# BluJoy-e.net
KiCad netlist of a schematic drawn in EAGLE
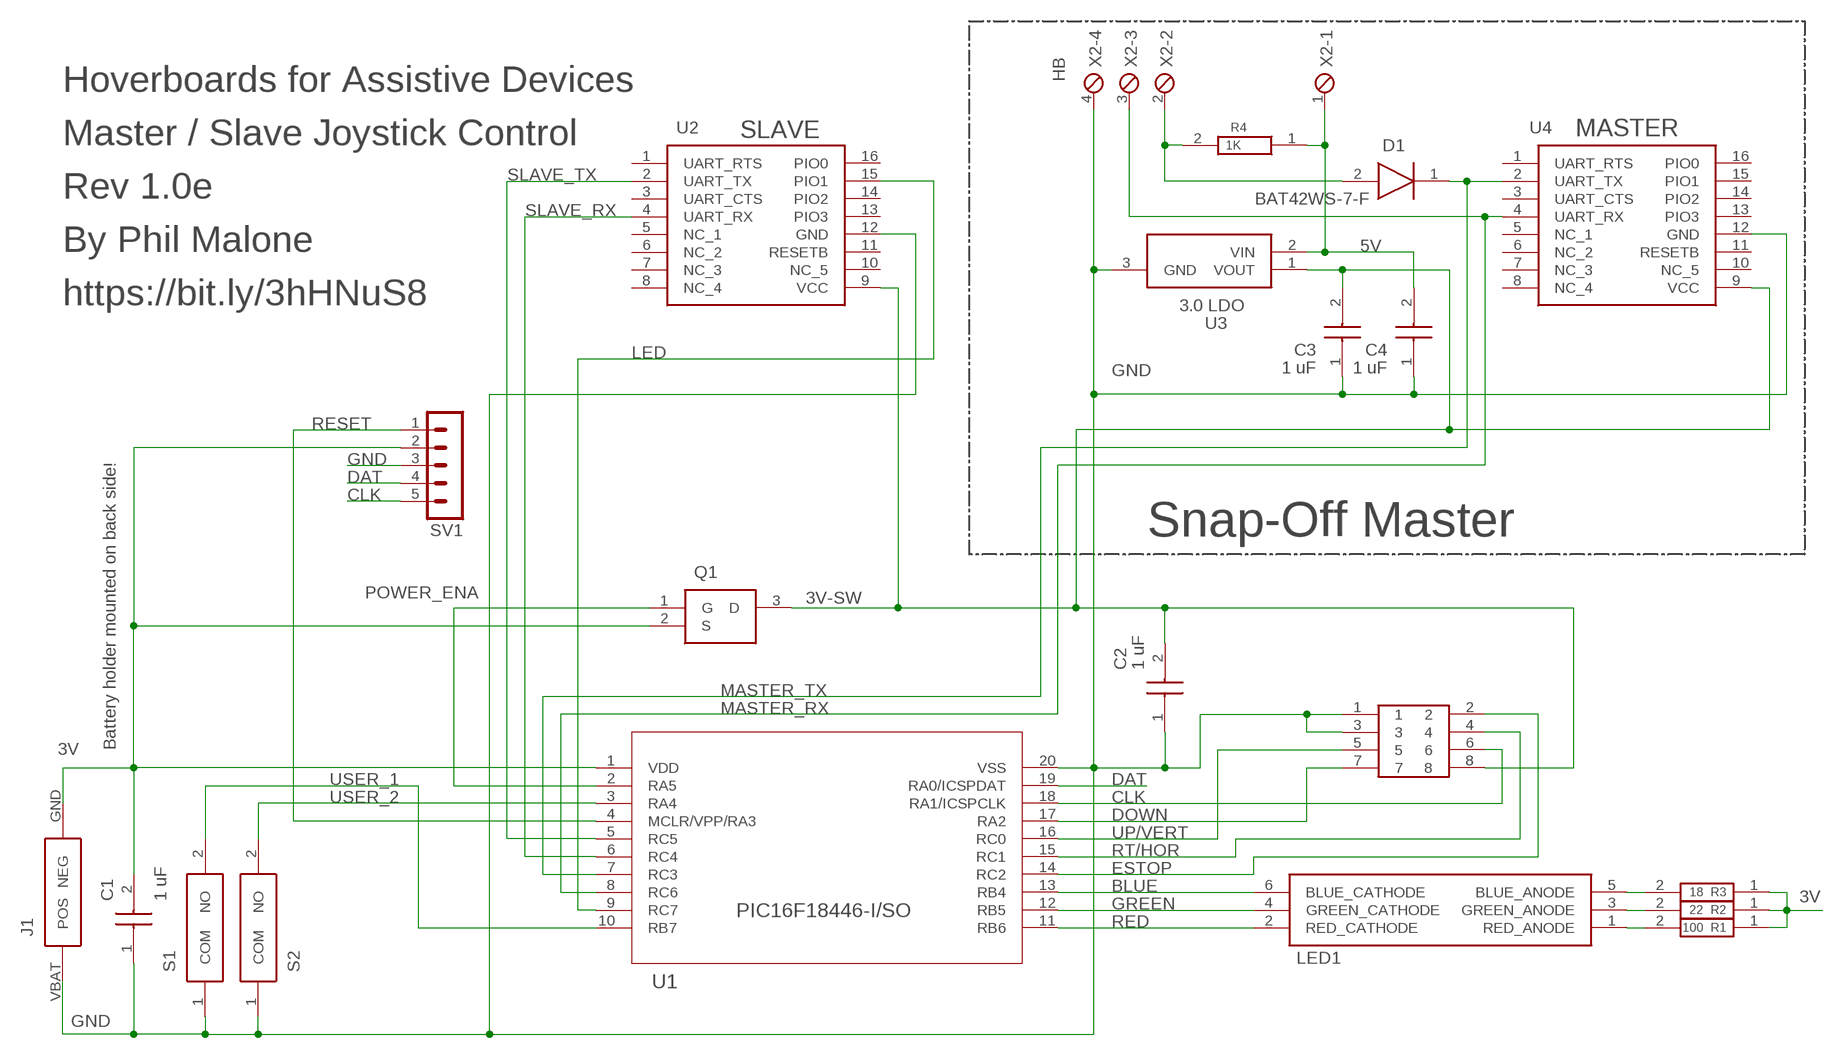
[diagram p0: schematic, sheet 1]

(export (version "E")
  (design (tool "Eeschema 10.0.6"))
  (components
    (comp (ref "C1")
      (value "1 uF")
      (footprint "eagle-import:CAPC1608X90N")
      (fields
        (field (name "MANUFACTURER_PART_NUMBER") "CC0603KRX7R7BB104")
        (field (name "MOUSER_PART_NUMBER") "603-CC603KRX7R7BB104")
        (field (name "RS_PART_NUMBER") "6698763")
      )
      (libsource (lib "eagle-import") (part "CC0603KRX7R7BB104"))
    )
    (comp (ref "C2")
      (value "1 uF")
      (footprint "eagle-import:CAPC1608X90N")
      (fields
        (field (name "MANUFACTURER_PART_NUMBER") "CC0603KRX7R7BB104")
        (field (name "MOUSER_PART_NUMBER") "603-CC603KRX7R7BB104")
        (field (name "RS_PART_NUMBER") "6698763")
      )
      (libsource (lib "eagle-import") (part "CC0603KRX7R7BB104"))
    )
    (comp (ref "C3")
      (value "1 uF")
      (footprint "eagle-import:CAPC1608X90N")
      (fields
        (field (name "MANUFACTURER_PART_NUMBER") "CC0603KRX7R7BB104")
        (field (name "MOUSER_PART_NUMBER") "603-CC603KRX7R7BB104")
        (field (name "RS_PART_NUMBER") "6698763")
      )
      (libsource (lib "eagle-import") (part "CC0603KRX7R7BB104"))
    )
    (comp (ref "C4")
      (value "1 uF")
      (footprint "eagle-import:CAPC1608X90N")
      (fields
        (field (name "MANUFACTURER_PART_NUMBER") "CC0603KRX7R7BB104")
        (field (name "MOUSER_PART_NUMBER") "603-CC603KRX7R7BB104")
        (field (name "RS_PART_NUMBER") "6698763")
      )
      (libsource (lib "eagle-import") (part "CC0603KRX7R7BB104"))
    )
    (comp (ref "D1")
      (value "BAT42WS-7-F")
      (footprint "eagle-import:SOD2513X120N")
      (fields (field (name "MOUSER_PART_NUMBER") "621-BAT42WS-F"))
      (libsource (lib "eagle-import") (part "BAT42WS-7-F"))
    )
    (comp (ref "J1")
      (value "2468")
      (footprint "eagle-import:2468")
      (fields (field (name "MOUSER_PART_NUMBER") "534-2468") (field (name "RS_PART_NUMBER") "2794965"))
      (libsource (lib "eagle-import") (part "2468"))
    )
    (comp (ref "LED1")
      (value "ASMB-TTF0-0A20B")
      (footprint "eagle-import:ASMBTTF00A20B")
      (fields (field (name "MOUSER_PART_NUMBER") "630-ASMB-TTF0-0A20B"))
      (libsource (lib "eagle-import") (part "ASMB-TTF0-0A20B"))
    )
    (comp (ref "Q1")
      (value "P-FET")
      (footprint "eagle-import:SOT96P237X111-3N")
      (fields
        (field (name "ARROW_PART_NUMBER") "NTR4171PT1G")
        (field (name "MOUSER_PART_NUMBER") "863-NTR4171PT1G")
      )
      (libsource (lib "eagle-import") (part "NTR4171PT1G"))
    )
    (comp (ref "R1")
      (value "100")
      (footprint "eagle-import:RESC1608X50N")
      (fields
        (field (name "MANUFACTURER_PART_NUMBER") "CRCW0603240RFKEB")
        (field (name "MOUSER_PART_NUMBER") "71-CRCW0603240RFKEB")
      )
      (libsource (lib "eagle-import") (part "CRCW0603240RFKEB"))
    )
    (comp (ref "R2")
      (value "22")
      (footprint "eagle-import:RESC1608X50N")
      (fields
        (field (name "MANUFACTURER_PART_NUMBER") "CRCW0603240RFKEB")
        (field (name "MOUSER_PART_NUMBER") "71-CRCW0603240RFKEB")
      )
      (libsource (lib "eagle-import") (part "CRCW0603240RFKEB"))
    )
    (comp (ref "R3")
      (value "18")
      (footprint "eagle-import:RESC1608X50N")
      (fields
        (field (name "MANUFACTURER_PART_NUMBER") "CRCW0603240RFKEB")
        (field (name "MOUSER_PART_NUMBER") "71-CRCW0603240RFKEB")
      )
      (libsource (lib "eagle-import") (part "CRCW0603240RFKEB"))
    )
    (comp (ref "R4")
      (value "1K")
      (footprint "eagle-import:RESC1608X50N")
      (fields
        (field (name "MANUFACTURER_PART_NUMBER") "CRCW0603240RFKEB")
        (field (name "MOUSER_PART_NUMBER") "71-CRCW0603240RFKEB")
      )
      (libsource (lib "eagle-import") (part "CRCW0603240RFKEB"))
    )
    (comp (ref "S1")
      (value "PTS636_SK25J_SMTR_LFS")
      (footprint "eagle-import:PTS636SK25JSMTRLFS")
      (fields
        (field (name "MANUFACTURER_PART_NUMBER") "PTS636 SK25J SMTR LFS")
        (field (name "MOUSER_PART_NUMBER") "611-PTS636SK25JSMTRL")
      )
      (libsource (lib "eagle-import") (part "PTS636_SK25J_SMTR_LFS"))
    )
    (comp (ref "S2")
      (value "PTS636_SK25J_SMTR_LFS")
      (footprint "eagle-import:PTS636SK25JSMTRLFS")
      (fields
        (field (name "MANUFACTURER_PART_NUMBER") "PTS636 SK25J SMTR LFS")
        (field (name "MOUSER_PART_NUMBER") "611-PTS636SK25JSMTRL")
      )
      (libsource (lib "eagle-import") (part "PTS636_SK25J_SMTR_LFS"))
    )
    (comp (ref "SV1")
      (value "PICKIT")
      (footprint "eagle-import:MA05-1")
      (libsource (lib "eagle-import") (part "PICKIT"))
    )
    (comp (ref "U$2")
      (value "PHOENIX3.5X8-B")
      (footprint "eagle-import:1751303")
      (libsource (lib "eagle-import") (part "PHOENIX3.5X8-B"))
    )
    (comp (ref "U1")
      (value "PIC16F18446-I/SO")
      (footprint "eagle-import:SOIC20_SO_MCH")
      (fields
        (field (name "MANUFACTURER_PART_NUMBER") "PIC16F15345-I/SO")
        (field (name "COPYRIGHT") "Copyright (C) 2018 Accelerated Designs. All rights reserved")
      )
      (libsource (lib "eagle-import") (part "PIC16F15345-I/SO"))
    )
    (comp (ref "U2")
      (value "HM-11")
      (footprint "eagle-import:HM-11-MODULE")
      (libsource (lib "eagle-import") (part "HM-11"))
    )
    (comp (ref "U3")
      (value "3.0 LDO")
      (footprint "eagle-import:SOT95P237X112-3N")
      (fields
        (field (name "ARROW_PART_NUMBER") "MCP1812AT-030/TT")
        (field (name "MOUSER_PART_NUMBER") "579-MCP1812AT-030/TT")
      )
      (libsource (lib "eagle-import") (part "MCP1812AT-030_TT"))
    )
    (comp (ref "U4")
      (value "HM-11")
      (footprint "eagle-import:HM-11-MODULE")
      (libsource (lib "eagle-import") (part "HM-11"))
    )
    (comp (ref "X2")
      (value "HB")
      (footprint "eagle-import:4POL254")
      (libsource (lib "eagle-import") (part "MPT4"))
    )
  )
  (nets
    (net (code "1") (name "/3V") (class "Default")
      (node (ref "C1") (pin "2") (pinfunction "C2_2") (pintype "bidirectional"))
      (node (ref "J1") (pin "GND") (pinfunction "NEG_GND") (pintype "bidirectional"))
      (node (ref "Q1") (pin "2") (pinfunction "S_2") (pintype "bidirectional"))
      (node (ref "R1") (pin "1") (pinfunction "1_1") (pintype "bidirectional"))
      (node (ref "R2") (pin "1") (pinfunction "1_1") (pintype "bidirectional"))
      (node (ref "R3") (pin "1") (pinfunction "1_1") (pintype "bidirectional"))
      (node (ref "SV1") (pin "2") (pinfunction "2_2") (pintype "passive"))
      (node (ref "U1") (pin "1") (pinfunction "VDD_1") (pintype "power_in"))
    )
    (net (code "2") (name "/3V-SW") (class "Default")
      (node (ref "C2") (pin "2") (pinfunction "C2_2") (pintype "bidirectional"))
      (node (ref "C3") (pin "2") (pinfunction "C2_2") (pintype "bidirectional"))
      (node (ref "Q1") (pin "3") (pinfunction "D_3") (pintype "bidirectional"))
      (node (ref "U$2") (pin "8") (pinfunction "8_8") (pintype "bidirectional"))
      (node (ref "U2") (pin "9") (pinfunction "VCC_9") (pintype "power_in"))
      (node (ref "U3") (pin "1") (pinfunction "VOUT_1") (pintype "power_in"))
      (node (ref "U4") (pin "9") (pinfunction "VCC_9") (pintype "power_in"))
    )
    (net (code "3") (name "/5V") (class "Default")
      (node (ref "C4") (pin "2") (pinfunction "C2_2") (pintype "bidirectional"))
      (node (ref "R4") (pin "1") (pinfunction "1_1") (pintype "bidirectional"))
      (node (ref "U3") (pin "2") (pinfunction "VIN_2") (pintype "power_in"))
      (node (ref "X2") (pin "1") (pinfunction "1_1") (pintype "passive"))
    )
    (net (code "4") (name "/BLUE") (class "Default")
      (node (ref "LED1") (pin "6") (pinfunction "BLUE_CATHODE_6") (pintype "bidirectional"))
      (node (ref "U1") (pin "13") (pinfunction "RB4_13") (pintype "bidirectional"))
    )
    (net (code "5") (name "/CLK") (class "Default")
      (node (ref "SV1") (pin "5") (pinfunction "5_5") (pintype "passive"))
      (node (ref "U$2") (pin "6") (pinfunction "6_6") (pintype "bidirectional"))
      (node (ref "U1") (pin "18") (pinfunction "RA1/ICSPCLK_18") (pintype "bidirectional"))
    )
    (net (code "6") (name "/DAT") (class "Default")
      (node (ref "SV1") (pin "4") (pinfunction "4_4") (pintype "passive"))
      (node (ref "U1") (pin "19") (pinfunction "RA0/ICSPDAT_19") (pintype "bidirectional"))
    )
    (net (code "7") (name "/DOWN") (class "Default")
      (node (ref "U$2") (pin "7") (pinfunction "7_7") (pintype "bidirectional"))
      (node (ref "U1") (pin "17") (pinfunction "RA2_17") (pintype "bidirectional"))
    )
    (net (code "8") (name "/ESTOP") (class "Default")
      (node (ref "U$2") (pin "2") (pinfunction "2_2") (pintype "bidirectional"))
      (node (ref "U1") (pin "14") (pinfunction "RC2_14") (pintype "bidirectional"))
    )
    (net (code "9") (name "/GND") (class "Default")
      (node (ref "C1") (pin "1") (pinfunction "C1_1") (pintype "bidirectional"))
      (node (ref "C2") (pin "1") (pinfunction "C1_1") (pintype "bidirectional"))
      (node (ref "C3") (pin "1") (pinfunction "C1_1") (pintype "bidirectional"))
      (node (ref "C4") (pin "1") (pinfunction "C1_1") (pintype "bidirectional"))
      (node (ref "J1") (pin "VBAT") (pinfunction "POS_VBAT") (pintype "bidirectional"))
      (node (ref "S1") (pin "1") (pinfunction "COM_1") (pintype "bidirectional"))
      (node (ref "S2") (pin "1") (pinfunction "COM_1") (pintype "bidirectional"))
      (node (ref "SV1") (pin "3") (pinfunction "3_3") (pintype "passive"))
      (node (ref "U$2") (pin "1") (pinfunction "1_1") (pintype "bidirectional"))
      (node (ref "U$2") (pin "3") (pinfunction "3_3") (pintype "bidirectional"))
      (node (ref "U1") (pin "20") (pinfunction "VSS_20") (pintype "passive"))
      (node (ref "U2") (pin "12") (pinfunction "GND_12") (pintype "power_in"))
      (node (ref "U3") (pin "3") (pinfunction "GND_3") (pintype "power_in"))
      (node (ref "U4") (pin "12") (pinfunction "GND_12") (pintype "power_in"))
      (node (ref "X2") (pin "4") (pinfunction "1_4") (pintype "passive"))
    )
    (net (code "10") (name "/GREEN") (class "Default")
      (node (ref "LED1") (pin "4") (pinfunction "GREEN_CATHODE_4") (pintype "bidirectional"))
      (node (ref "U1") (pin "12") (pinfunction "RB5_12") (pintype "bidirectional"))
    )
    (net (code "11") (name "/LED") (class "Default")
      (node (ref "U1") (pin "9") (pinfunction "RC7_9") (pintype "bidirectional"))
      (node (ref "U2") (pin "15") (pinfunction "PIO1_15") (pintype "bidirectional"))
    )
    (net (code "12") (name "/MASTER_RX") (class "Default")
      (node (ref "U1") (pin "8") (pinfunction "RC6_8") (pintype "bidirectional"))
      (node (ref "U4") (pin "4") (pinfunction "UART_RX_4") (pintype "bidirectional"))
      (node (ref "X2") (pin "3") (pinfunction "1_3") (pintype "passive"))
    )
    (net (code "13") (name "/MASTER_TX") (class "Default")
      (node (ref "D1") (pin "1") (pinfunction "K_1") (pintype "bidirectional"))
      (node (ref "U1") (pin "7") (pinfunction "RC3_7") (pintype "bidirectional"))
      (node (ref "U4") (pin "2") (pinfunction "UART_TX_2") (pintype "bidirectional"))
    )
    (net (code "14") (name "/POWER_ENA") (class "Default")
      (node (ref "Q1") (pin "1") (pinfunction "G_1") (pintype "bidirectional"))
      (node (ref "U1") (pin "2") (pinfunction "RA5_2") (pintype "bidirectional"))
    )
    (net (code "15") (name "/RED") (class "Default")
      (node (ref "LED1") (pin "2") (pinfunction "RED_CATHODE_2") (pintype "bidirectional"))
      (node (ref "U1") (pin "11") (pinfunction "RB6_11") (pintype "bidirectional"))
    )
    (net (code "16") (name "/RESET") (class "Default")
      (node (ref "SV1") (pin "1") (pinfunction "1_1") (pintype "passive"))
      (node (ref "U1") (pin "4") (pinfunction "MCLR/VPP/RA3_4") (pintype "power_in"))
    )
    (net (code "17") (name "/RT{slash}HOR") (class "Default")
      (node (ref "U$2") (pin "4") (pinfunction "4_4") (pintype "bidirectional"))
      (node (ref "U1") (pin "15") (pinfunction "RC1_15") (pintype "bidirectional"))
    )
    (net (code "18") (name "/SLAVE_RX") (class "Default")
      (node (ref "U1") (pin "6") (pinfunction "RC4_6") (pintype "bidirectional"))
      (node (ref "U2") (pin "4") (pinfunction "UART_RX_4") (pintype "bidirectional"))
    )
    (net (code "19") (name "/SLAVE_TX") (class "Default")
      (node (ref "U1") (pin "5") (pinfunction "RC5_5") (pintype "bidirectional"))
      (node (ref "U2") (pin "2") (pinfunction "UART_TX_2") (pintype "bidirectional"))
    )
    (net (code "20") (name "/UP{slash}VERT") (class "Default")
      (node (ref "U$2") (pin "5") (pinfunction "5_5") (pintype "bidirectional"))
      (node (ref "U1") (pin "16") (pinfunction "RC0_16") (pintype "bidirectional"))
    )
    (net (code "21") (name "/USER_1") (class "Default")
      (node (ref "S1") (pin "2") (pinfunction "NO_2") (pintype "bidirectional"))
      (node (ref "U1") (pin "10") (pinfunction "RB7_10") (pintype "bidirectional"))
    )
    (net (code "22") (name "/USER_2") (class "Default")
      (node (ref "S2") (pin "2") (pinfunction "NO_2") (pintype "bidirectional"))
      (node (ref "U1") (pin "3") (pinfunction "RA4_3") (pintype "bidirectional"))
    )
    (net (code "23") (name "Net-(D1-A)") (class "Default")
      (node (ref "D1") (pin "2") (pinfunction "A_2") (pintype "bidirectional"))
      (node (ref "R4") (pin "2") (pinfunction "2_2") (pintype "bidirectional"))
      (node (ref "X2") (pin "2") (pinfunction "1_2") (pintype "passive"))
    )
    (net (code "24") (name "Net-(LED1-BLUE_ANODE)") (class "Default")
      (node (ref "LED1") (pin "5") (pinfunction "BLUE_ANODE_5") (pintype "bidirectional"))
      (node (ref "R3") (pin "2") (pinfunction "2_2") (pintype "bidirectional"))
    )
    (net (code "25") (name "Net-(LED1-GREEN_ANODE)") (class "Default")
      (node (ref "LED1") (pin "3") (pinfunction "GREEN_ANODE_3") (pintype "bidirectional"))
      (node (ref "R2") (pin "2") (pinfunction "2_2") (pintype "bidirectional"))
    )
    (net (code "26") (name "Net-(LED1-RED_ANODE)") (class "Default")
      (node (ref "LED1") (pin "1") (pinfunction "RED_ANODE_1") (pintype "bidirectional"))
      (node (ref "R1") (pin "2") (pinfunction "2_2") (pintype "bidirectional"))
    )
    (net (code "27") (name "unconnected-(U2-NC_1-Pad5)") (class "Default")
      (node (ref "U2") (pin "5") (pinfunction "NC_1_5") (pintype "bidirectional"))
    )
    (net (code "28") (name "unconnected-(U2-NC_2-Pad6)") (class "Default")
      (node (ref "U2") (pin "6") (pinfunction "NC_2_6") (pintype "bidirectional"))
    )
    (net (code "29") (name "unconnected-(U2-NC_3-Pad7)") (class "Default")
      (node (ref "U2") (pin "7") (pinfunction "NC_3_7") (pintype "bidirectional"))
    )
    (net (code "30") (name "unconnected-(U2-NC_4-Pad8)") (class "Default")
      (node (ref "U2") (pin "8") (pinfunction "NC_4_8") (pintype "bidirectional"))
    )
    (net (code "31") (name "unconnected-(U2-NC_5-Pad10)") (class "Default")
      (node (ref "U2") (pin "10") (pinfunction "NC_5_10") (pintype "bidirectional"))
    )
    (net (code "32") (name "unconnected-(U2-PIO0-Pad16)") (class "Default")
      (node (ref "U2") (pin "16") (pinfunction "PIO0_16") (pintype "bidirectional"))
    )
    (net (code "33") (name "unconnected-(U2-PIO2-Pad14)") (class "Default")
      (node (ref "U2") (pin "14") (pinfunction "PIO2_14") (pintype "bidirectional"))
    )
    (net (code "34") (name "unconnected-(U2-PIO3-Pad13)") (class "Default")
      (node (ref "U2") (pin "13") (pinfunction "PIO3_13") (pintype "bidirectional"))
    )
    (net (code "35") (name "unconnected-(U2-RESETB-Pad11)") (class "Default")
      (node (ref "U2") (pin "11") (pinfunction "RESETB_11") (pintype "bidirectional"))
    )
    (net (code "36") (name "unconnected-(U2-UART_CTS-Pad3)") (class "Default")
      (node (ref "U2") (pin "3") (pinfunction "UART_CTS_3") (pintype "bidirectional"))
    )
    (net (code "37") (name "unconnected-(U2-UART_RTS-Pad1)") (class "Default")
      (node (ref "U2") (pin "1") (pinfunction "UART_RTS_1") (pintype "bidirectional"))
    )
    (net (code "38") (name "unconnected-(U4-NC_1-Pad5)") (class "Default")
      (node (ref "U4") (pin "5") (pinfunction "NC_1_5") (pintype "bidirectional"))
    )
    (net (code "39") (name "unconnected-(U4-NC_2-Pad6)") (class "Default")
      (node (ref "U4") (pin "6") (pinfunction "NC_2_6") (pintype "bidirectional"))
    )
    (net (code "40") (name "unconnected-(U4-NC_3-Pad7)") (class "Default")
      (node (ref "U4") (pin "7") (pinfunction "NC_3_7") (pintype "bidirectional"))
    )
    (net (code "41") (name "unconnected-(U4-NC_4-Pad8)") (class "Default")
      (node (ref "U4") (pin "8") (pinfunction "NC_4_8") (pintype "bidirectional"))
    )
    (net (code "42") (name "unconnected-(U4-NC_5-Pad10)") (class "Default")
      (node (ref "U4") (pin "10") (pinfunction "NC_5_10") (pintype "bidirectional"))
    )
    (net (code "43") (name "unconnected-(U4-PIO0-Pad16)") (class "Default")
      (node (ref "U4") (pin "16") (pinfunction "PIO0_16") (pintype "bidirectional"))
    )
    (net (code "44") (name "unconnected-(U4-PIO1-Pad15)") (class "Default")
      (node (ref "U4") (pin "15") (pinfunction "PIO1_15") (pintype "bidirectional"))
    )
    (net (code "45") (name "unconnected-(U4-PIO2-Pad14)") (class "Default")
      (node (ref "U4") (pin "14") (pinfunction "PIO2_14") (pintype "bidirectional"))
    )
    (net (code "46") (name "unconnected-(U4-PIO3-Pad13)") (class "Default")
      (node (ref "U4") (pin "13") (pinfunction "PIO3_13") (pintype "bidirectional"))
    )
    (net (code "47") (name "unconnected-(U4-RESETB-Pad11)") (class "Default")
      (node (ref "U4") (pin "11") (pinfunction "RESETB_11") (pintype "bidirectional"))
    )
    (net (code "48") (name "unconnected-(U4-UART_CTS-Pad3)") (class "Default")
      (node (ref "U4") (pin "3") (pinfunction "UART_CTS_3") (pintype "bidirectional"))
    )
    (net (code "49") (name "unconnected-(U4-UART_RTS-Pad1)") (class "Default")
      (node (ref "U4") (pin "1") (pinfunction "UART_RTS_1") (pintype "bidirectional"))
    )
  )
)
